# LED-drive-Red.net
KiCad netlist of a schematic drawn in Altium Designer
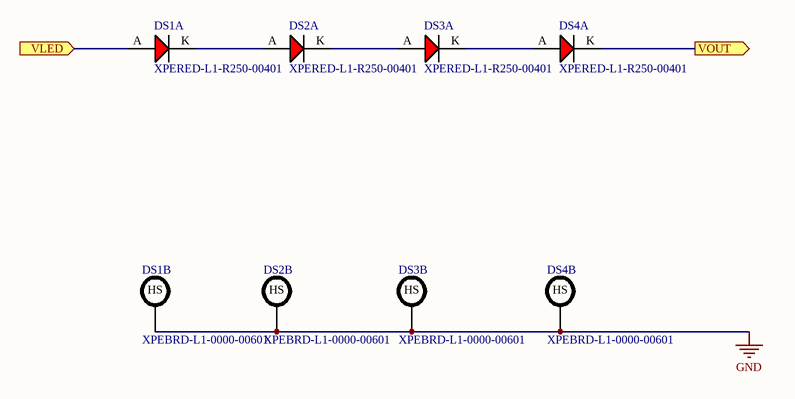
[diagram p0: LED-drive-Red.SchDoc]

(export (version "E")
  (design (tool "Eeschema 10.0.6"))
  (components
    (comp (ref "DS1")
      (value "XPERED-L1-R250-00401")
      (footprint "Cree XLamp XP-E2 (red and green LED)")
      (description "LED, Cree XLamp XP-E2 Series, Red, 630 nm, 130 °, 62 lm, 1 A")
      (libsource (lib "TSAL") (part "XPEBRD-L1-0000-00601"))
    )
    (comp (ref "DS2")
      (value "XPERED-L1-R250-00401")
      (footprint "Cree XLamp XP-E2 (red and green LED)")
      (description "LED, Cree XLamp XP-E2 Series, Red, 630 nm, 130 °, 62 lm, 1 A")
      (libsource (lib "TSAL") (part "XPEBRD-L1-0000-00601"))
    )
    (comp (ref "DS3")
      (value "XPERED-L1-R250-00401")
      (footprint "Cree XLamp XP-E2 (red and green LED)")
      (description "LED, Cree XLamp XP-E2 Series, Red, 630 nm, 130 °, 62 lm, 1 A")
      (libsource (lib "TSAL") (part "XPEBRD-L1-0000-00601"))
    )
    (comp (ref "DS4")
      (value "XPERED-L1-R250-00401")
      (footprint "Cree XLamp XP-E2 (red and green LED)")
      (description "LED, Cree XLamp XP-E2 Series, Red, 630 nm, 130 °, 62 lm, 1 A")
      (libsource (lib "TSAL") (part "XPEBRD-L1-0000-00601"))
    )
  )
  (nets
    (net (code "1") (name "/VLED") (class "Default")
      (node (ref "DS1") (pin "A") (pinfunction "A_A") (pintype "passive"))
    )
    (net (code "2") (name "/VOUT") (class "Default")
      (node (ref "DS4") (pin "K") (pinfunction "K_K") (pintype "passive"))
    )
    (net (code "3") (name "GND") (class "Default")
      (node (ref "DS1") (pin "HS") (pinfunction "HS_HS") (pintype "passive"))
      (node (ref "DS2") (pin "HS") (pinfunction "HS_HS") (pintype "passive"))
      (node (ref "DS3") (pin "HS") (pinfunction "HS_HS") (pintype "passive"))
      (node (ref "DS4") (pin "HS") (pinfunction "HS_HS") (pintype "passive"))
    )
    (net (code "4") (name "Net-(DS1-PadK)") (class "Default")
      (node (ref "DS1") (pin "K") (pinfunction "K_K") (pintype "passive"))
      (node (ref "DS2") (pin "A") (pinfunction "A_A") (pintype "passive"))
    )
    (net (code "5") (name "Net-(DS2-PadK)") (class "Default")
      (node (ref "DS2") (pin "K") (pinfunction "K_K") (pintype "passive"))
      (node (ref "DS3") (pin "A") (pinfunction "A_A") (pintype "passive"))
    )
    (net (code "6") (name "Net-(DS3-PadK)") (class "Default")
      (node (ref "DS3") (pin "K") (pinfunction "K_K") (pintype "passive"))
      (node (ref "DS4") (pin "A") (pinfunction "A_A") (pintype "passive"))
    )
  )
)
